# eeprom_temp_sens.net
KiCad netlist of a schematic drawn in Altium Designer
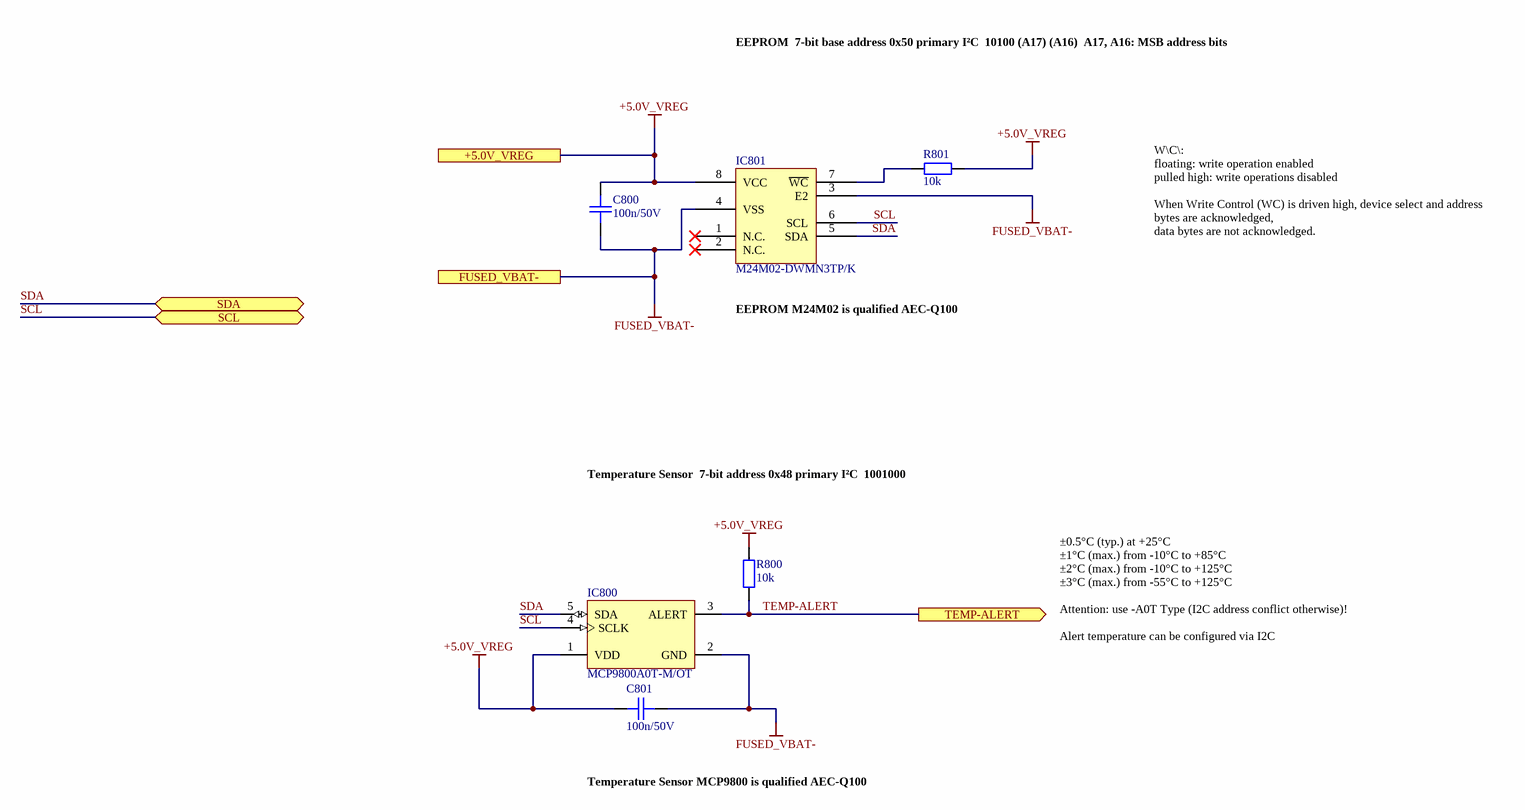
[diagram p0: eeprom_temp_sens.SchDoc]

(export (version "E")
  (design (tool "Eeschema 10.0.6"))
  (components
    (comp (ref "C800")
      (value "100n/50V")
      (footprint "CAPC1608X08N")
      (description "MLCC")
      (fields (field (name "PART NUMBER") "gen_C_ceramic_100n_50V_X7R_0603"))
      (libsource (lib "OE750") (part "C"))
    )
    (comp (ref "C801")
      (value "100n/50V")
      (footprint "CAPC1608X08N")
      (description "MLCC")
      (fields (field (name "PART NUMBER") "gen_C_ceramic_100n_50V_X7R_0603"))
      (libsource (lib "OE750") (part "C"))
    )
    (comp (ref "IC800")
      (value "MCP9800A0T-M/OT")
      (footprint "SOT-23-OT5_L")
      (libsource (lib "Altium Content Vault") (part "SEN-TEMP-MCP980X-5"))
    )
    (comp (ref "IC801")
      (value "M24M02-DWMN3TP/K")
      (footprint "SOIC127P600X175-8N")
      (description "Automotive 2-Mbit serial I²C \r\nbus EEPROM with 1 MHz clock")
      (fields (field (name "MANUFACTURER") "STMicroelectronics"))
      (libsource (lib "OE750") (part "M24M02-DWMN3TP/K"))
    )
    (comp (ref "R800")
      (value "10k")
      (footprint "RESC1608X05N")
      (description "SMD Resistor 10k 0603")
      (fields (field (name "PART NUMBER") "gen_R_10k_0603") (field (name "TOLERANCE") "1%"))
      (libsource (lib "OE750") (part "R"))
    )
    (comp (ref "R801")
      (value "10k")
      (footprint "RESC1608X05N")
      (description "SMD Resistor 10k 0603")
      (fields (field (name "PART NUMBER") "gen_R_10k_0603") (field (name "TOLERANCE") "1%"))
      (libsource (lib "OE750") (part "R"))
    )
  )
  (nets
    (net (code "1") (name "+5.0V_VREG") (class "Default")
      (node (ref "C800") (pin "2") (pinfunction "2_2") (pintype "passive"))
      (node (ref "C801") (pin "2") (pinfunction "2_2") (pintype "passive"))
      (node (ref "IC800") (pin "1") (pinfunction "VDD_1") (pintype "power_in"))
      (node (ref "IC801") (pin "8") (pinfunction "VCC_8") (pintype "power_in"))
      (node (ref "R800") (pin "2") (pinfunction "2_2") (pintype "passive"))
      (node (ref "R801") (pin "2") (pinfunction "2_2") (pintype "passive"))
    )
    (net (code "2") (name "/SCL") (class "Default")
      (node (ref "IC800") (pin "4") (pinfunction "SCLK_4") (pintype "input"))
      (node (ref "IC801") (pin "6") (pinfunction "SCL_6") (pintype "passive"))
    )
    (net (code "3") (name "/SDA") (class "Default")
      (node (ref "IC800") (pin "5") (pinfunction "SDA_5") (pintype "bidirectional"))
      (node (ref "IC801") (pin "5") (pinfunction "SDA_5") (pintype "passive"))
    )
    (net (code "4") (name "/TEMP-ALERT") (class "Default")
      (node (ref "IC800") (pin "3") (pinfunction "ALERT_3") (pintype "open_collector"))
      (node (ref "R800") (pin "1") (pinfunction "1_1") (pintype "passive"))
    )
    (net (code "5") (name "FUSED_VBAT-") (class "Default")
      (node (ref "C800") (pin "1") (pinfunction "1_1") (pintype "passive"))
      (node (ref "C801") (pin "1") (pinfunction "1_1") (pintype "passive"))
      (node (ref "IC800") (pin "2") (pinfunction "GND_2") (pintype "power_in"))
      (node (ref "IC801") (pin "3") (pinfunction "E2_3") (pintype "passive"))
      (node (ref "IC801") (pin "4") (pinfunction "VSS_4") (pintype "power_in"))
    )
    (net (code "6") (name "Net-(IC801-~{WC})") (class "Default")
      (node (ref "IC801") (pin "7") (pinfunction "~{WC}_7") (pintype "passive"))
      (node (ref "R801") (pin "1") (pinfunction "1_1") (pintype "passive"))
    )
    (net (code "7") (name "unconnected-(IC801-N.C.-Pad1)") (class "Default")
      (node (ref "IC801") (pin "1") (pinfunction "N.C._1") (pintype "passive+no_connect"))
    )
    (net (code "8") (name "unconnected-(IC801-N.C.-Pad2)") (class "Default")
      (node (ref "IC801") (pin "2") (pinfunction "N.C._2") (pintype "passive+no_connect"))
    )
  )
)
